# TPS54202.net
KiCad netlist of a schematic drawn in Altium Designer
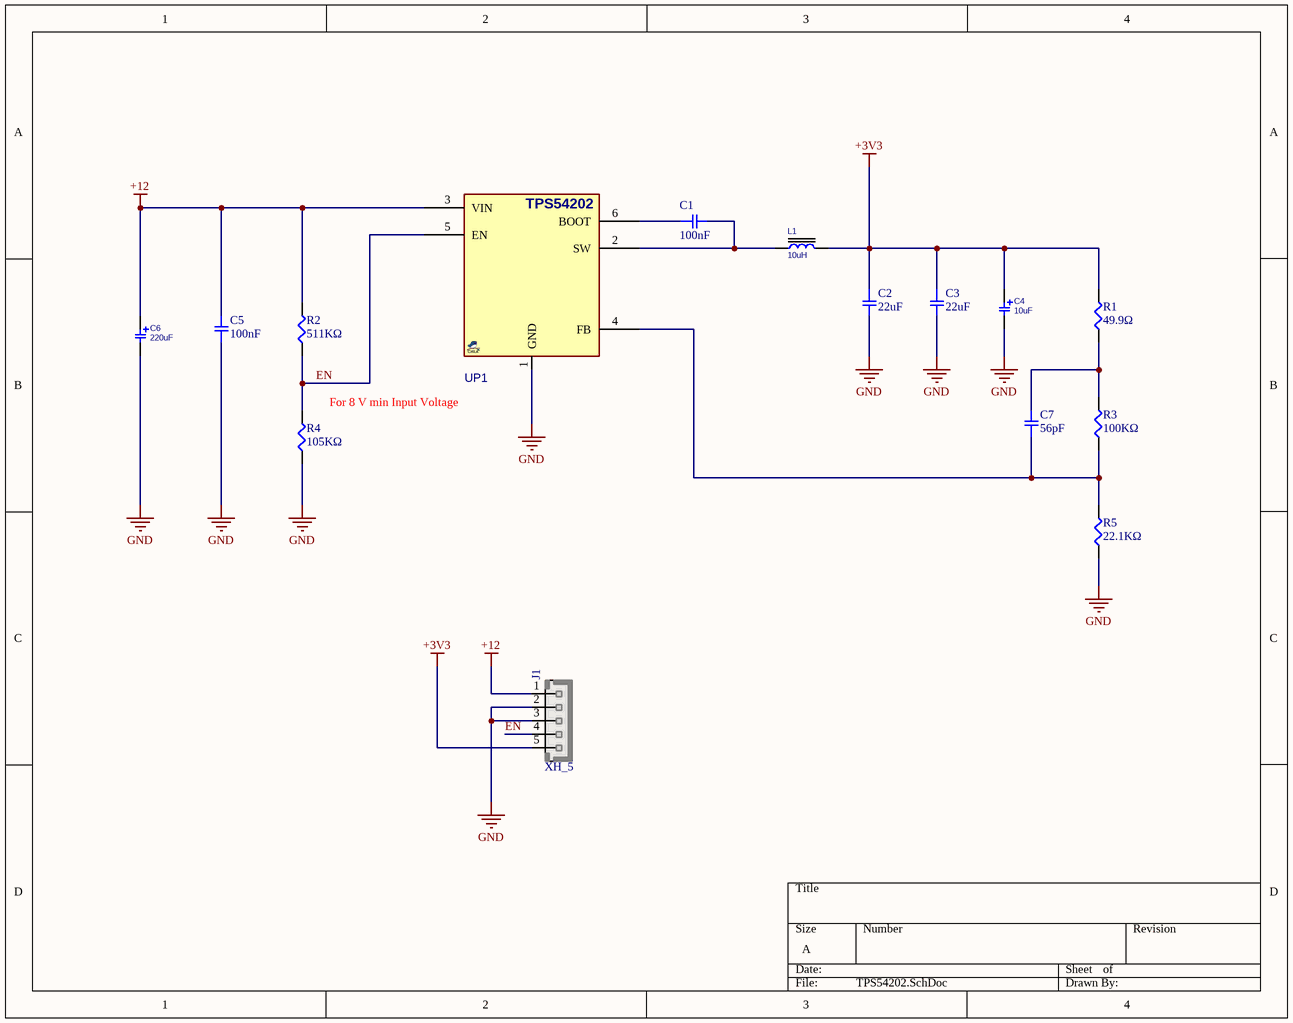
[diagram p0: TPS54202.SchDoc]

(export (version "E")
  (design (tool "Eeschema 10.0.6"))
  (components
    (comp (ref "C1")
      (value "100nF")
      (footprint "SMD-0805C")
      (description "CAP CER 100nF 50V X7T 0805")
      (fields
        (field (name "DIGI-KEY PART NUMBER") "490-13986-1-ND")
        (field (name "PART NUMBER") "GC321AD72E103KX01D")
      )
      (libsource (lib "capacitor_murata_0805") (part "GC321AD72E103KX01D"))
    )
    (comp (ref "C2")
      (value "22uF")
      (footprint "SMD-1206C")
      (description "CAP CER 22UF 50V X5R 1206")
      (fields
        (field (name "DIGI-KEY PART NUMBER") "490-13989-1-ND")
        (field (name "PART NUMBER") "GC331AD72E333KX01D")
      )
      (libsource (lib "capacitor_murata_1206") (part "GC331AD72E333KX01D"))
    )
    (comp (ref "C3")
      (value "22uF")
      (footprint "SMD-1206C")
      (description "CAP CER 22UF 50V X5R 1206")
      (fields
        (field (name "DIGI-KEY PART NUMBER") "490-13989-1-ND")
        (field (name "PART NUMBER") "GC331AD72E333KX01D")
      )
      (libsource (lib "capacitor_murata_1206") (part "GC331AD72E333KX01D"))
    )
    (comp (ref "C4")
      (value "10uF")
      (footprint "C_TN_3216")
      (description "CAP, SMD, TAN")
      (fields (field (name "MANF") "VISHAY") (field (name "MANF_P#") "T55A106M6R3C0300"))
      (libsource (lib "chila ") (part "CAP_SMD_TAN_10uF_6.3V"))
    )
    (comp (ref "C5")
      (value "100nF")
      (footprint "SMD-0805C")
      (description "CAP CER 100nF 50V X7T 0805")
      (fields
        (field (name "DIGI-KEY PART NUMBER") "490-13986-1-ND")
        (field (name "PART NUMBER") "GC321AD72E103KX01D")
      )
      (libsource (lib "capacitor_murata_0805") (part "GC321AD72E103KX01D"))
    )
    (comp (ref "C6")
      (value "220uF")
      (footprint "C_TN_7343")
      (description "CAP, SMD, TAN")
      (fields (field (name "MANF") "VISHAY") (field (name "MANF_P#") "T55D227M6R3C0035"))
      (libsource (lib "chila ") (part "CAP_SMD_TAN_220uF"))
    )
    (comp (ref "C7")
      (value "56pF")
      (footprint "SMD-0805C")
      (description "CAP CER 100nF 50V X7T 0805")
      (fields
        (field (name "DIGI-KEY PART NUMBER") "490-13986-1-ND")
        (field (name "PART NUMBER") "GC321AD72E103KX01D")
      )
      (libsource (lib "capacitor_murata_0805") (part "GC321AD72E103KX01D"))
    )
    (comp (ref "J1")
      (value "XH_5")
      (footprint "XH_5")
      (description "JST-XH pitch: 2.5mm")
      (fields (field (name "MANF_P#") "JST-B5B-XHA") (field (name "MANF") "JST"))
      (libsource (lib "chila ") (part "XH_5"))
    )
    (comp (ref "L1")
      (value "10uH")
      (footprint "F1812")
      (description "INDUCTOR, 10uH 2A, 38mOhm, 2626")
      (fields (field (name "MANF_P#") "SRR6038-100Y") (field (name "MANF") "Bourns"))
      (libsource (lib "chila ") (part "IND_SMD_10uH_2A"))
    )
    (comp (ref "R1")
      (value "49.9Ω")
      (footprint "SMD-0805-RES")
      (description "49.9Ω / 0805")
      (fields (field (name "PART NUMBER") "ERJ-6BQF1R0V") (field (name "DIGI-KEY PART NUMBER") "P17499CT-ND"))
      (libsource (lib "Panasonic_ERJ_0805") (part "ERJ-6BQF1R0V"))
    )
    (comp (ref "R2")
      (value "511KΩ")
      (footprint "SMD-0805-RES")
      (description "511K 0805")
      (fields (field (name "PART NUMBER") "ERJ-6BQF1R0V") (field (name "DIGI-KEY PART NUMBER") "P17499CT-ND"))
      (libsource (lib "Panasonic_ERJ_0805") (part "ERJ-6BQF1R0V"))
    )
    (comp (ref "R3")
      (value "100KΩ")
      (footprint "SMD-0805-RES")
      (description "100KΩ / 0805")
      (fields (field (name "PART NUMBER") "ERJ-6BQF1R0V") (field (name "DIGI-KEY PART NUMBER") "P17499CT-ND"))
      (libsource (lib "Panasonic_ERJ_0805") (part "ERJ-6BQF1R0V"))
    )
    (comp (ref "R4")
      (value "105KΩ")
      (footprint "SMD-0805-RES")
      (description "105KΩ 0805")
      (fields (field (name "PART NUMBER") "ERJ-6BQF1R0V") (field (name "DIGI-KEY PART NUMBER") "P17499CT-ND"))
      (libsource (lib "Panasonic_ERJ_0805") (part "ERJ-6BQF1R0V"))
    )
    (comp (ref "R5")
      (value "22.1KΩ")
      (footprint "SMD-0805-RES")
      (description "22.1KΩ  0805")
      (fields (field (name "PART NUMBER") "ERJ-6BQF1R0V") (field (name "DIGI-KEY PART NUMBER") "P17499CT-ND"))
      (libsource (lib "Panasonic_ERJ_0805") (part "ERJ-6BQF1R0V"))
    )
    (comp (ref "UP1")
      (value "TPS54202")
      (footprint "SOT23_6")
      (description "REG, Switching, Buck, 2A, ADJ, 0.5MHz, 4.5~28VIN, SOT23-6")
      (fields (field (name "MANF") "TI") (field (name "MANF_P#") "TPS54202DDC, TPS54202HDDC"))
      (libsource (lib "chila ") (part "VREG_TPS54202_SOT23-6"))
    )
  )
  (nets
    (net (code "1") (name "+3V3") (class "Default")
      (node (ref "C2") (pin "1") (pinfunction "1_1") (pintype "passive"))
      (node (ref "C3") (pin "1") (pinfunction "1_1") (pintype "passive"))
      (node (ref "C4") (pin "1") (pinfunction "1_1") (pintype "passive"))
      (node (ref "J1") (pin "5") (pinfunction "5_5") (pintype "passive"))
      (node (ref "L1") (pin "2") (pinfunction "2_2") (pintype "passive"))
      (node (ref "R1") (pin "2") (pinfunction "2_2") (pintype "passive"))
    )
    (net (code "2") (name "+12") (class "Default")
      (node (ref "C5") (pin "2") (pinfunction "2_2") (pintype "passive"))
      (node (ref "C6") (pin "1") (pinfunction "1_1") (pintype "passive"))
      (node (ref "J1") (pin "1") (pinfunction "1_1") (pintype "passive"))
      (node (ref "R2") (pin "2") (pinfunction "2_2") (pintype "passive"))
      (node (ref "UP1") (pin "3") (pinfunction "VIN_3") (pintype "power_in"))
    )
    (net (code "3") (name "/EN") (class "Default")
      (node (ref "J1") (pin "4") (pinfunction "4_4") (pintype "passive"))
      (node (ref "R2") (pin "1") (pinfunction "1_1") (pintype "passive"))
      (node (ref "R4") (pin "2") (pinfunction "2_2") (pintype "passive"))
      (node (ref "UP1") (pin "5") (pinfunction "EN_5") (pintype "passive"))
    )
    (net (code "4") (name "GND") (class "Default")
      (node (ref "C2") (pin "2") (pinfunction "2_2") (pintype "passive"))
      (node (ref "C3") (pin "2") (pinfunction "2_2") (pintype "passive"))
      (node (ref "C4") (pin "2") (pinfunction "2_2") (pintype "passive"))
      (node (ref "C5") (pin "1") (pinfunction "1_1") (pintype "passive"))
      (node (ref "C6") (pin "2") (pinfunction "2_2") (pintype "passive"))
      (node (ref "J1") (pin "2") (pinfunction "2_2") (pintype "passive"))
      (node (ref "J1") (pin "3") (pinfunction "3_3") (pintype "passive"))
      (node (ref "R4") (pin "1") (pinfunction "1_1") (pintype "passive"))
      (node (ref "R5") (pin "1") (pinfunction "1_1") (pintype "passive"))
      (node (ref "UP1") (pin "1") (pinfunction "GND_1") (pintype "power_in"))
    )
    (net (code "5") (name "Net-(C7-Pad2)") (class "Default")
      (node (ref "C7") (pin "2") (pinfunction "2_2") (pintype "passive"))
      (node (ref "R1") (pin "1") (pinfunction "1_1") (pintype "passive"))
      (node (ref "R3") (pin "2") (pinfunction "2_2") (pintype "passive"))
    )
    (net (code "6") (name "Net-(UP1-BOOT)") (class "Default")
      (node (ref "C1") (pin "1") (pinfunction "1_1") (pintype "passive"))
      (node (ref "UP1") (pin "6") (pinfunction "BOOT_6") (pintype "passive"))
    )
    (net (code "7") (name "Net-(UP1-FB)") (class "Default")
      (node (ref "C7") (pin "1") (pinfunction "1_1") (pintype "passive"))
      (node (ref "R3") (pin "1") (pinfunction "1_1") (pintype "passive"))
      (node (ref "R5") (pin "2") (pinfunction "2_2") (pintype "passive"))
      (node (ref "UP1") (pin "4") (pinfunction "FB_4") (pintype "passive"))
    )
    (net (code "8") (name "Net-(UP1-SW)") (class "Default")
      (node (ref "C1") (pin "2") (pinfunction "2_2") (pintype "passive"))
      (node (ref "L1") (pin "1") (pinfunction "1_1") (pintype "passive"))
      (node (ref "UP1") (pin "2") (pinfunction "SW_2") (pintype "passive"))
    )
  )
)
